# LCD_TO_ARDUINO.net
KiCad netlist of a schematic drawn in EAGLE
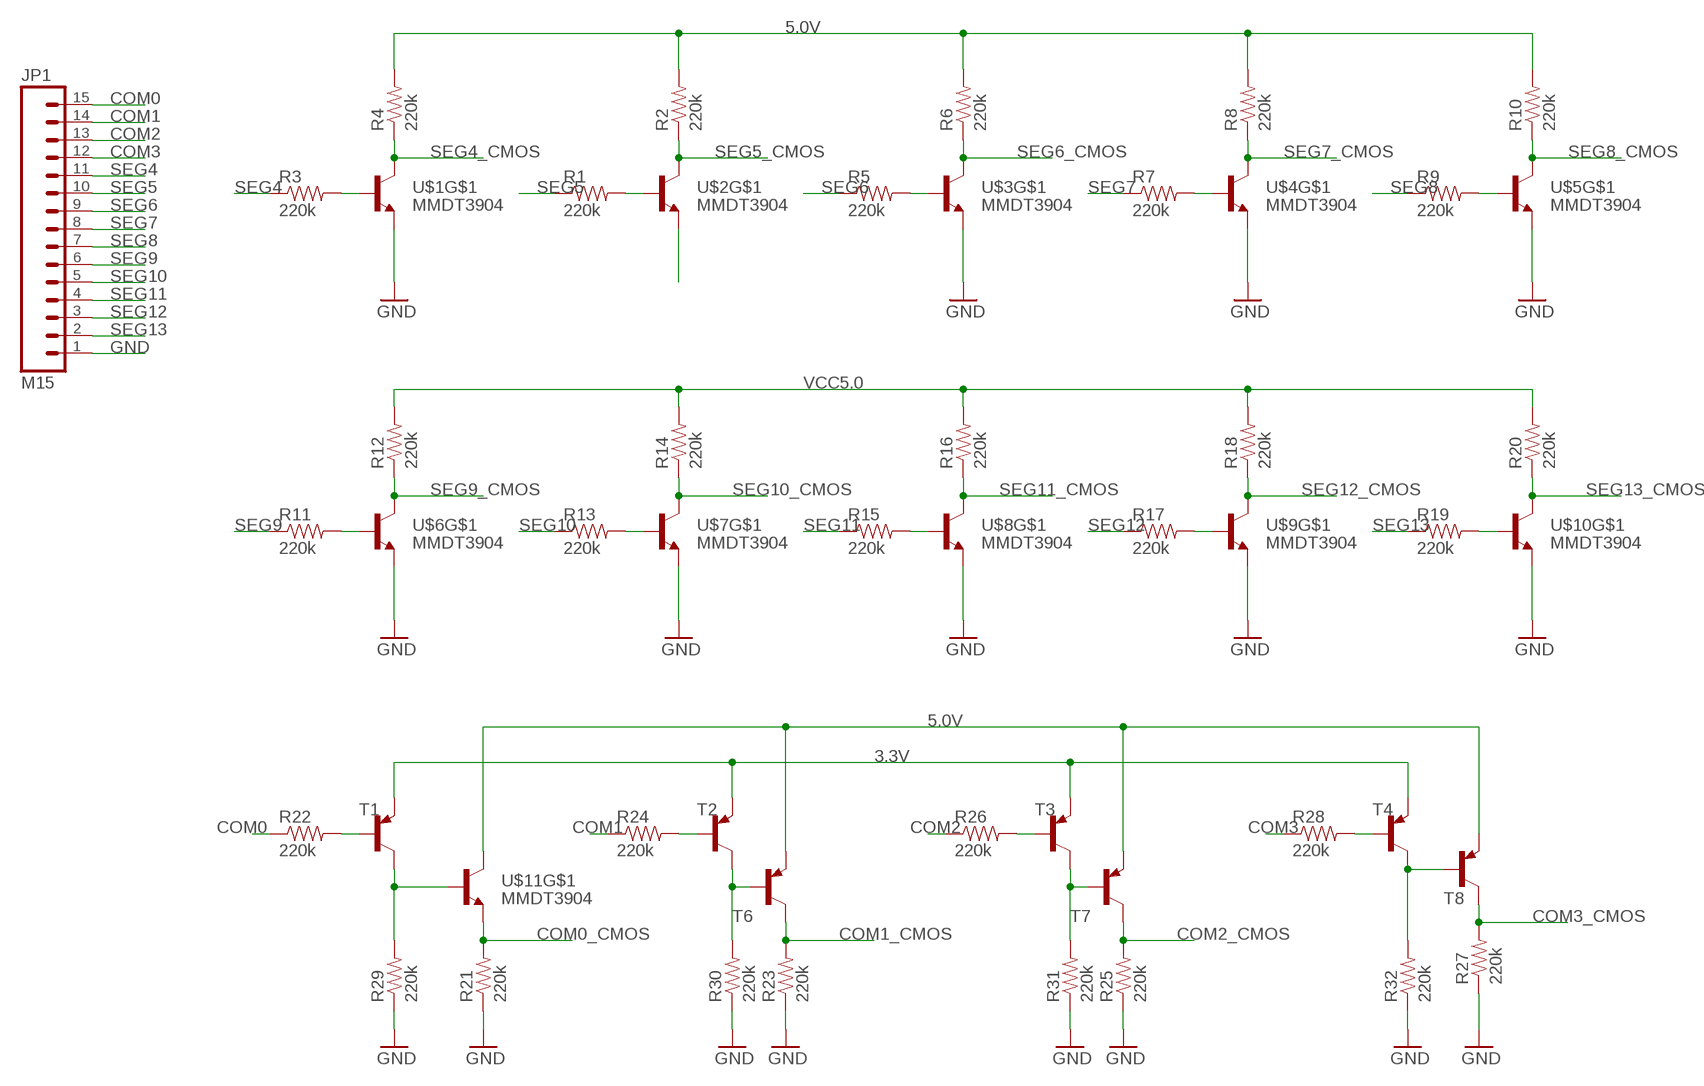
[diagram p0: schematic, sheet 1]

(export (version "E")
  (design (tool "Eeschema 10.0.6"))
  (components
    (comp (ref "JP1")
      (value "M15")
      (footprint "eagle-import:1X15")
      (libsource (lib "eagle-import") (part "M15"))
    )
    (comp (ref "R1")
      (value "220k")
      (footprint "eagle-import:0805")
      (libsource (lib "eagle-import") (part "RESISTOR0805-RES"))
    )
    (comp (ref "R2")
      (value "220k")
      (footprint "eagle-import:0805")
      (libsource (lib "eagle-import") (part "RESISTOR0805-RES"))
    )
    (comp (ref "R3")
      (value "220k")
      (footprint "eagle-import:0805")
      (libsource (lib "eagle-import") (part "RESISTOR0805-RES"))
    )
    (comp (ref "R4")
      (value "220k")
      (footprint "eagle-import:0805")
      (libsource (lib "eagle-import") (part "RESISTOR0805-RES"))
    )
    (comp (ref "R5")
      (value "220k")
      (footprint "eagle-import:0805")
      (libsource (lib "eagle-import") (part "RESISTOR0805-RES"))
    )
    (comp (ref "R6")
      (value "220k")
      (footprint "eagle-import:0805")
      (libsource (lib "eagle-import") (part "RESISTOR0805-RES"))
    )
    (comp (ref "R7")
      (value "220k")
      (footprint "eagle-import:0805")
      (libsource (lib "eagle-import") (part "RESISTOR0805-RES"))
    )
    (comp (ref "R8")
      (value "220k")
      (footprint "eagle-import:0805")
      (libsource (lib "eagle-import") (part "RESISTOR0805-RES"))
    )
    (comp (ref "R9")
      (value "220k")
      (footprint "eagle-import:0805")
      (libsource (lib "eagle-import") (part "RESISTOR0805-RES"))
    )
    (comp (ref "R10")
      (value "220k")
      (footprint "eagle-import:0805")
      (libsource (lib "eagle-import") (part "RESISTOR0805-RES"))
    )
    (comp (ref "R11")
      (value "220k")
      (footprint "eagle-import:0805")
      (libsource (lib "eagle-import") (part "RESISTOR0805-RES"))
    )
    (comp (ref "R12")
      (value "220k")
      (footprint "eagle-import:0805")
      (libsource (lib "eagle-import") (part "RESISTOR0805-RES"))
    )
    (comp (ref "R13")
      (value "220k")
      (footprint "eagle-import:0805")
      (libsource (lib "eagle-import") (part "RESISTOR0805-RES"))
    )
    (comp (ref "R14")
      (value "220k")
      (footprint "eagle-import:0805")
      (libsource (lib "eagle-import") (part "RESISTOR0805-RES"))
    )
    (comp (ref "R15")
      (value "220k")
      (footprint "eagle-import:0805")
      (libsource (lib "eagle-import") (part "RESISTOR0805-RES"))
    )
    (comp (ref "R16")
      (value "220k")
      (footprint "eagle-import:0805")
      (libsource (lib "eagle-import") (part "RESISTOR0805-RES"))
    )
    (comp (ref "R17")
      (value "220k")
      (footprint "eagle-import:0805")
      (libsource (lib "eagle-import") (part "RESISTOR0805-RES"))
    )
    (comp (ref "R18")
      (value "220k")
      (footprint "eagle-import:0805")
      (libsource (lib "eagle-import") (part "RESISTOR0805-RES"))
    )
    (comp (ref "R19")
      (value "220k")
      (footprint "eagle-import:0805")
      (libsource (lib "eagle-import") (part "RESISTOR0805-RES"))
    )
    (comp (ref "R20")
      (value "220k")
      (footprint "eagle-import:0805")
      (libsource (lib "eagle-import") (part "RESISTOR0805-RES"))
    )
    (comp (ref "R21")
      (value "220k")
      (footprint "eagle-import:0805")
      (libsource (lib "eagle-import") (part "RESISTOR0805-RES"))
    )
    (comp (ref "R22")
      (value "220k")
      (footprint "eagle-import:0805")
      (libsource (lib "eagle-import") (part "RESISTOR0805-RES"))
    )
    (comp (ref "R23")
      (value "220k")
      (footprint "eagle-import:0805")
      (libsource (lib "eagle-import") (part "RESISTOR0805-RES"))
    )
    (comp (ref "R24")
      (value "220k")
      (footprint "eagle-import:0805")
      (libsource (lib "eagle-import") (part "RESISTOR0805-RES"))
    )
    (comp (ref "R25")
      (value "220k")
      (footprint "eagle-import:0805")
      (libsource (lib "eagle-import") (part "RESISTOR0805-RES"))
    )
    (comp (ref "R26")
      (value "220k")
      (footprint "eagle-import:0805")
      (libsource (lib "eagle-import") (part "RESISTOR0805-RES"))
    )
    (comp (ref "R27")
      (value "220k")
      (footprint "eagle-import:0805")
      (libsource (lib "eagle-import") (part "RESISTOR0805-RES"))
    )
    (comp (ref "R28")
      (value "220k")
      (footprint "eagle-import:0805")
      (libsource (lib "eagle-import") (part "RESISTOR0805-RES"))
    )
    (comp (ref "R29")
      (value "220k")
      (footprint "eagle-import:0805")
      (libsource (lib "eagle-import") (part "RESISTOR0805-RES"))
    )
    (comp (ref "R30")
      (value "220k")
      (footprint "eagle-import:0805")
      (libsource (lib "eagle-import") (part "RESISTOR0805-RES"))
    )
    (comp (ref "R31")
      (value "220k")
      (footprint "eagle-import:0805")
      (libsource (lib "eagle-import") (part "RESISTOR0805-RES"))
    )
    (comp (ref "R32")
      (value "220k")
      (footprint "eagle-import:0805")
      (libsource (lib "eagle-import") (part "RESISTOR0805-RES"))
    )
    (comp (ref "T1")
      (value "MMBT3906LT1-PNP-SOT23-BEC")
      (footprint "eagle-import:SOT23-BEC")
      (libsource (lib "eagle-import") (part "-PNP-SOT23-BECMMBT3906LT1"))
    )
    (comp (ref "T2")
      (value "MMBT3906LT1-PNP-SOT23-BEC")
      (footprint "eagle-import:SOT23-BEC")
      (libsource (lib "eagle-import") (part "-PNP-SOT23-BECMMBT3906LT1"))
    )
    (comp (ref "T3")
      (value "MMBT3906LT1-PNP-SOT23-BEC")
      (footprint "eagle-import:SOT23-BEC")
      (libsource (lib "eagle-import") (part "-PNP-SOT23-BECMMBT3906LT1"))
    )
    (comp (ref "T4")
      (value "MMBT3906LT1-PNP-SOT23-BEC")
      (footprint "eagle-import:SOT23-BEC")
      (libsource (lib "eagle-import") (part "-PNP-SOT23-BECMMBT3906LT1"))
    )
    (comp (ref "T6")
      (value "MMBT3906LT1-PNP-SOT23-BEC")
      (footprint "eagle-import:SOT23-BEC")
      (libsource (lib "eagle-import") (part "-PNP-SOT23-BECMMBT3906LT1"))
    )
    (comp (ref "T7")
      (value "MMBT3906LT1-PNP-SOT23-BEC")
      (footprint "eagle-import:SOT23-BEC")
      (libsource (lib "eagle-import") (part "-PNP-SOT23-BECMMBT3906LT1"))
    )
    (comp (ref "T8")
      (value "MMBT3906LT1-PNP-SOT23-BEC")
      (footprint "eagle-import:SOT23-BEC")
      (libsource (lib "eagle-import") (part "-PNP-SOT23-BECMMBT3906LT1"))
    )
    (comp (ref "U$1")
      (value "MMDT3904")
      (footprint "eagle-import:SOT363")
      (libsource (lib "eagle-import") (part "MMDT3904"))
    )
    (comp (ref "U$2")
      (value "MMDT3904")
      (footprint "eagle-import:SOT363")
      (libsource (lib "eagle-import") (part "MMDT3904"))
    )
    (comp (ref "U$3")
      (value "MMDT3904")
      (footprint "eagle-import:SOT363")
      (libsource (lib "eagle-import") (part "MMDT3904"))
    )
    (comp (ref "U$4")
      (value "MMDT3904")
      (footprint "eagle-import:SOT363")
      (libsource (lib "eagle-import") (part "MMDT3904"))
    )
    (comp (ref "U$5")
      (value "MMDT3904")
      (footprint "eagle-import:SOT363")
      (libsource (lib "eagle-import") (part "MMDT3904"))
    )
    (comp (ref "U$6")
      (value "MMDT3904")
      (footprint "eagle-import:SOT363")
      (libsource (lib "eagle-import") (part "MMDT3904"))
    )
    (comp (ref "U$7")
      (value "MMDT3904")
      (footprint "eagle-import:SOT363")
      (libsource (lib "eagle-import") (part "MMDT3904"))
    )
    (comp (ref "U$8")
      (value "MMDT3904")
      (footprint "eagle-import:SOT363")
      (libsource (lib "eagle-import") (part "MMDT3904"))
    )
    (comp (ref "U$9")
      (value "MMDT3904")
      (footprint "eagle-import:SOT363")
      (libsource (lib "eagle-import") (part "MMDT3904"))
    )
    (comp (ref "U$10")
      (value "MMDT3904")
      (footprint "eagle-import:SOT363")
      (libsource (lib "eagle-import") (part "MMDT3904"))
    )
    (comp (ref "U$11")
      (value "MMDT3904")
      (footprint "eagle-import:SOT363")
      (libsource (lib "eagle-import") (part "MMDT3904"))
    )
  )
  (nets
    (net (code "1") (name "/3.3V") (class "Default")
      (node (ref "T1") (pin "E") (pinfunction "E_E") (pintype "passive"))
      (node (ref "T2") (pin "E") (pinfunction "E_E") (pintype "passive"))
      (node (ref "T3") (pin "E") (pinfunction "E_E") (pintype "passive"))
      (node (ref "T4") (pin "E") (pinfunction "E_E") (pintype "passive"))
    )
    (net (code "2") (name "/5.0V") (class "Default")
      (node (ref "R10") (pin "2") (pinfunction "2_2") (pintype "passive"))
      (node (ref "R2") (pin "2") (pinfunction "2_2") (pintype "passive"))
      (node (ref "R4") (pin "2") (pinfunction "2_2") (pintype "passive"))
      (node (ref "R6") (pin "2") (pinfunction "2_2") (pintype "passive"))
      (node (ref "R8") (pin "2") (pinfunction "2_2") (pintype "passive"))
      (node (ref "T6") (pin "E") (pinfunction "E_E") (pintype "passive"))
      (node (ref "T7") (pin "E") (pinfunction "E_E") (pintype "passive"))
      (node (ref "T8") (pin "E") (pinfunction "E_E") (pintype "passive"))
      (node (ref "U$11") (pin "3") (pinfunction "C_3") (pintype "passive"))
    )
    (net (code "3") (name "/COM0") (class "Default")
      (node (ref "JP1") (pin "15") (pinfunction "15_15") (pintype "passive"))
      (node (ref "R22") (pin "1") (pinfunction "1_1") (pintype "passive"))
    )
    (net (code "4") (name "/COM0_CMOS") (class "Default")
      (node (ref "R21") (pin "2") (pinfunction "2_2") (pintype "passive"))
      (node (ref "U$11") (pin "4") (pinfunction "E_4") (pintype "passive"))
    )
    (net (code "5") (name "/COM1") (class "Default")
      (node (ref "JP1") (pin "14") (pinfunction "14_14") (pintype "passive"))
      (node (ref "R24") (pin "1") (pinfunction "1_1") (pintype "passive"))
    )
    (net (code "6") (name "/COM1_CMOS") (class "Default")
      (node (ref "R23") (pin "2") (pinfunction "2_2") (pintype "passive"))
      (node (ref "T6") (pin "C") (pinfunction "C_C") (pintype "passive"))
    )
    (net (code "7") (name "/COM2") (class "Default")
      (node (ref "JP1") (pin "13") (pinfunction "13_13") (pintype "passive"))
      (node (ref "R26") (pin "1") (pinfunction "1_1") (pintype "passive"))
    )
    (net (code "8") (name "/COM2_CMOS") (class "Default")
      (node (ref "R25") (pin "2") (pinfunction "2_2") (pintype "passive"))
      (node (ref "T7") (pin "C") (pinfunction "C_C") (pintype "passive"))
    )
    (net (code "9") (name "/COM3") (class "Default")
      (node (ref "JP1") (pin "12") (pinfunction "12_12") (pintype "passive"))
      (node (ref "R28") (pin "1") (pinfunction "1_1") (pintype "passive"))
    )
    (net (code "10") (name "/COM3_CMOS") (class "Default")
      (node (ref "R27") (pin "2") (pinfunction "2_2") (pintype "passive"))
      (node (ref "T8") (pin "C") (pinfunction "C_C") (pintype "passive"))
    )
    (net (code "11") (name "/SEG4") (class "Default")
      (node (ref "JP1") (pin "11") (pinfunction "11_11") (pintype "passive"))
      (node (ref "R3") (pin "1") (pinfunction "1_1") (pintype "passive"))
    )
    (net (code "12") (name "/SEG4_CMOS") (class "Default")
      (node (ref "R4") (pin "1") (pinfunction "1_1") (pintype "passive"))
      (node (ref "U$1") (pin "3") (pinfunction "C_3") (pintype "passive"))
    )
    (net (code "13") (name "/SEG5") (class "Default")
      (node (ref "JP1") (pin "10") (pinfunction "10_10") (pintype "passive"))
      (node (ref "R1") (pin "1") (pinfunction "1_1") (pintype "passive"))
    )
    (net (code "14") (name "/SEG5_CMOS") (class "Default")
      (node (ref "R2") (pin "1") (pinfunction "1_1") (pintype "passive"))
      (node (ref "U$2") (pin "3") (pinfunction "C_3") (pintype "passive"))
    )
    (net (code "15") (name "/SEG6") (class "Default")
      (node (ref "JP1") (pin "9") (pinfunction "9_9") (pintype "passive"))
      (node (ref "R5") (pin "1") (pinfunction "1_1") (pintype "passive"))
    )
    (net (code "16") (name "/SEG6_CMOS") (class "Default")
      (node (ref "R6") (pin "1") (pinfunction "1_1") (pintype "passive"))
      (node (ref "U$3") (pin "3") (pinfunction "C_3") (pintype "passive"))
    )
    (net (code "17") (name "/SEG7") (class "Default")
      (node (ref "JP1") (pin "8") (pinfunction "8_8") (pintype "passive"))
      (node (ref "R7") (pin "1") (pinfunction "1_1") (pintype "passive"))
    )
    (net (code "18") (name "/SEG7_CMOS") (class "Default")
      (node (ref "R8") (pin "1") (pinfunction "1_1") (pintype "passive"))
      (node (ref "U$4") (pin "3") (pinfunction "C_3") (pintype "passive"))
    )
    (net (code "19") (name "/SEG8") (class "Default")
      (node (ref "JP1") (pin "7") (pinfunction "7_7") (pintype "passive"))
      (node (ref "R9") (pin "1") (pinfunction "1_1") (pintype "passive"))
    )
    (net (code "20") (name "/SEG8_CMOS") (class "Default")
      (node (ref "R10") (pin "1") (pinfunction "1_1") (pintype "passive"))
      (node (ref "U$5") (pin "3") (pinfunction "C_3") (pintype "passive"))
    )
    (net (code "21") (name "/SEG9") (class "Default")
      (node (ref "JP1") (pin "6") (pinfunction "6_6") (pintype "passive"))
      (node (ref "R11") (pin "1") (pinfunction "1_1") (pintype "passive"))
    )
    (net (code "22") (name "/SEG9_CMOS") (class "Default")
      (node (ref "R12") (pin "1") (pinfunction "1_1") (pintype "passive"))
      (node (ref "U$6") (pin "3") (pinfunction "C_3") (pintype "passive"))
    )
    (net (code "23") (name "/SEG10") (class "Default")
      (node (ref "JP1") (pin "5") (pinfunction "5_5") (pintype "passive"))
      (node (ref "R13") (pin "1") (pinfunction "1_1") (pintype "passive"))
    )
    (net (code "24") (name "/SEG10_CMOS") (class "Default")
      (node (ref "R14") (pin "1") (pinfunction "1_1") (pintype "passive"))
      (node (ref "U$7") (pin "3") (pinfunction "C_3") (pintype "passive"))
    )
    (net (code "25") (name "/SEG11") (class "Default")
      (node (ref "JP1") (pin "4") (pinfunction "4_4") (pintype "passive"))
      (node (ref "R15") (pin "1") (pinfunction "1_1") (pintype "passive"))
    )
    (net (code "26") (name "/SEG11_CMOS") (class "Default")
      (node (ref "R16") (pin "1") (pinfunction "1_1") (pintype "passive"))
      (node (ref "U$8") (pin "3") (pinfunction "C_3") (pintype "passive"))
    )
    (net (code "27") (name "/SEG12") (class "Default")
      (node (ref "JP1") (pin "3") (pinfunction "3_3") (pintype "passive"))
      (node (ref "R17") (pin "1") (pinfunction "1_1") (pintype "passive"))
    )
    (net (code "28") (name "/SEG12_CMOS") (class "Default")
      (node (ref "R18") (pin "1") (pinfunction "1_1") (pintype "passive"))
      (node (ref "U$9") (pin "3") (pinfunction "C_3") (pintype "passive"))
    )
    (net (code "29") (name "/SEG13") (class "Default")
      (node (ref "JP1") (pin "2") (pinfunction "2_2") (pintype "passive"))
      (node (ref "R19") (pin "1") (pinfunction "1_1") (pintype "passive"))
    )
    (net (code "30") (name "/SEG13_CMOS") (class "Default")
      (node (ref "R20") (pin "1") (pinfunction "1_1") (pintype "passive"))
      (node (ref "U$10") (pin "3") (pinfunction "C_3") (pintype "passive"))
    )
    (net (code "31") (name "/VCC5.0") (class "Default")
      (node (ref "R12") (pin "2") (pinfunction "2_2") (pintype "passive"))
      (node (ref "R14") (pin "2") (pinfunction "2_2") (pintype "passive"))
      (node (ref "R16") (pin "2") (pinfunction "2_2") (pintype "passive"))
      (node (ref "R18") (pin "2") (pinfunction "2_2") (pintype "passive"))
      (node (ref "R20") (pin "2") (pinfunction "2_2") (pintype "passive"))
    )
    (net (code "32") (name "GND") (class "Default")
      (node (ref "JP1") (pin "1") (pinfunction "1_1") (pintype "passive"))
      (node (ref "R21") (pin "1") (pinfunction "1_1") (pintype "passive"))
      (node (ref "R23") (pin "1") (pinfunction "1_1") (pintype "passive"))
      (node (ref "R25") (pin "1") (pinfunction "1_1") (pintype "passive"))
      (node (ref "R27") (pin "1") (pinfunction "1_1") (pintype "passive"))
      (node (ref "R29") (pin "1") (pinfunction "1_1") (pintype "passive"))
      (node (ref "R30") (pin "1") (pinfunction "1_1") (pintype "passive"))
      (node (ref "R31") (pin "1") (pinfunction "1_1") (pintype "passive"))
      (node (ref "R32") (pin "1") (pinfunction "1_1") (pintype "passive"))
      (node (ref "U$1") (pin "4") (pinfunction "E_4") (pintype "passive"))
      (node (ref "U$10") (pin "4") (pinfunction "E_4") (pintype "passive"))
      (node (ref "U$3") (pin "4") (pinfunction "E_4") (pintype "passive"))
      (node (ref "U$4") (pin "4") (pinfunction "E_4") (pintype "passive"))
      (node (ref "U$5") (pin "4") (pinfunction "E_4") (pintype "passive"))
      (node (ref "U$6") (pin "4") (pinfunction "E_4") (pintype "passive"))
      (node (ref "U$7") (pin "4") (pinfunction "E_4") (pintype "passive"))
      (node (ref "U$8") (pin "4") (pinfunction "E_4") (pintype "passive"))
      (node (ref "U$9") (pin "4") (pinfunction "E_4") (pintype "passive"))
    )
    (net (code "33") (name "Net-(R22-Pad2)") (class "Default")
      (node (ref "R22") (pin "2") (pinfunction "2_2") (pintype "passive"))
      (node (ref "T1") (pin "B") (pinfunction "B_B") (pintype "passive"))
    )
    (net (code "34") (name "Net-(R24-Pad2)") (class "Default")
      (node (ref "R24") (pin "2") (pinfunction "2_2") (pintype "passive"))
      (node (ref "T2") (pin "B") (pinfunction "B_B") (pintype "passive"))
    )
    (net (code "35") (name "Net-(R26-Pad2)") (class "Default")
      (node (ref "R26") (pin "2") (pinfunction "2_2") (pintype "passive"))
      (node (ref "T3") (pin "B") (pinfunction "B_B") (pintype "passive"))
    )
    (net (code "36") (name "Net-(R28-Pad2)") (class "Default")
      (node (ref "R28") (pin "2") (pinfunction "2_2") (pintype "passive"))
      (node (ref "T4") (pin "B") (pinfunction "B_B") (pintype "passive"))
    )
    (net (code "37") (name "Net-(R30-Pad2)") (class "Default")
      (node (ref "R30") (pin "2") (pinfunction "2_2") (pintype "passive"))
      (node (ref "T2") (pin "C") (pinfunction "C_C") (pintype "passive"))
      (node (ref "T6") (pin "B") (pinfunction "B_B") (pintype "passive"))
    )
    (net (code "38") (name "Net-(R31-Pad2)") (class "Default")
      (node (ref "R31") (pin "2") (pinfunction "2_2") (pintype "passive"))
      (node (ref "T3") (pin "C") (pinfunction "C_C") (pintype "passive"))
      (node (ref "T7") (pin "B") (pinfunction "B_B") (pintype "passive"))
    )
    (net (code "39") (name "Net-(R32-Pad2)") (class "Default")
      (node (ref "R32") (pin "2") (pinfunction "2_2") (pintype "passive"))
      (node (ref "T4") (pin "C") (pinfunction "C_C") (pintype "passive"))
      (node (ref "T8") (pin "B") (pinfunction "B_B") (pintype "passive"))
    )
    (net (code "40") (name "Net-(U$1A-B)") (class "Default")
      (node (ref "R3") (pin "2") (pinfunction "2_2") (pintype "passive"))
      (node (ref "U$1") (pin "5") (pinfunction "B_5") (pintype "passive"))
    )
    (net (code "41") (name "Net-(U$2A-B)") (class "Default")
      (node (ref "R1") (pin "2") (pinfunction "2_2") (pintype "passive"))
      (node (ref "U$2") (pin "5") (pinfunction "B_5") (pintype "passive"))
    )
    (net (code "42") (name "Net-(U$3A-B)") (class "Default")
      (node (ref "R5") (pin "2") (pinfunction "2_2") (pintype "passive"))
      (node (ref "U$3") (pin "5") (pinfunction "B_5") (pintype "passive"))
    )
    (net (code "43") (name "Net-(U$4A-B)") (class "Default")
      (node (ref "R7") (pin "2") (pinfunction "2_2") (pintype "passive"))
      (node (ref "U$4") (pin "5") (pinfunction "B_5") (pintype "passive"))
    )
    (net (code "44") (name "Net-(U$5A-B)") (class "Default")
      (node (ref "R9") (pin "2") (pinfunction "2_2") (pintype "passive"))
      (node (ref "U$5") (pin "5") (pinfunction "B_5") (pintype "passive"))
    )
    (net (code "45") (name "Net-(U$6A-B)") (class "Default")
      (node (ref "R11") (pin "2") (pinfunction "2_2") (pintype "passive"))
      (node (ref "U$6") (pin "5") (pinfunction "B_5") (pintype "passive"))
    )
    (net (code "46") (name "Net-(U$7A-B)") (class "Default")
      (node (ref "R13") (pin "2") (pinfunction "2_2") (pintype "passive"))
      (node (ref "U$7") (pin "5") (pinfunction "B_5") (pintype "passive"))
    )
    (net (code "47") (name "Net-(U$8A-B)") (class "Default")
      (node (ref "R15") (pin "2") (pinfunction "2_2") (pintype "passive"))
      (node (ref "U$8") (pin "5") (pinfunction "B_5") (pintype "passive"))
    )
    (net (code "48") (name "Net-(U$9A-B)") (class "Default")
      (node (ref "R17") (pin "2") (pinfunction "2_2") (pintype "passive"))
      (node (ref "U$9") (pin "5") (pinfunction "B_5") (pintype "passive"))
    )
    (net (code "49") (name "Net-(U$10A-B)") (class "Default")
      (node (ref "R19") (pin "2") (pinfunction "2_2") (pintype "passive"))
      (node (ref "U$10") (pin "5") (pinfunction "B_5") (pintype "passive"))
    )
    (net (code "50") (name "Net-(U$11A-B)") (class "Default")
      (node (ref "R29") (pin "2") (pinfunction "2_2") (pintype "passive"))
      (node (ref "T1") (pin "C") (pinfunction "C_C") (pintype "passive"))
      (node (ref "U$11") (pin "5") (pinfunction "B_5") (pintype "passive"))
    )
    (net (code "51") (name "unconnected-(U$2A-E-Pad4)") (class "Default")
      (node (ref "U$2") (pin "4") (pinfunction "E_4") (pintype "passive"))
    )
  )
)
